# Sheet1.net
KiCad netlist of a schematic drawn in Altium Designer
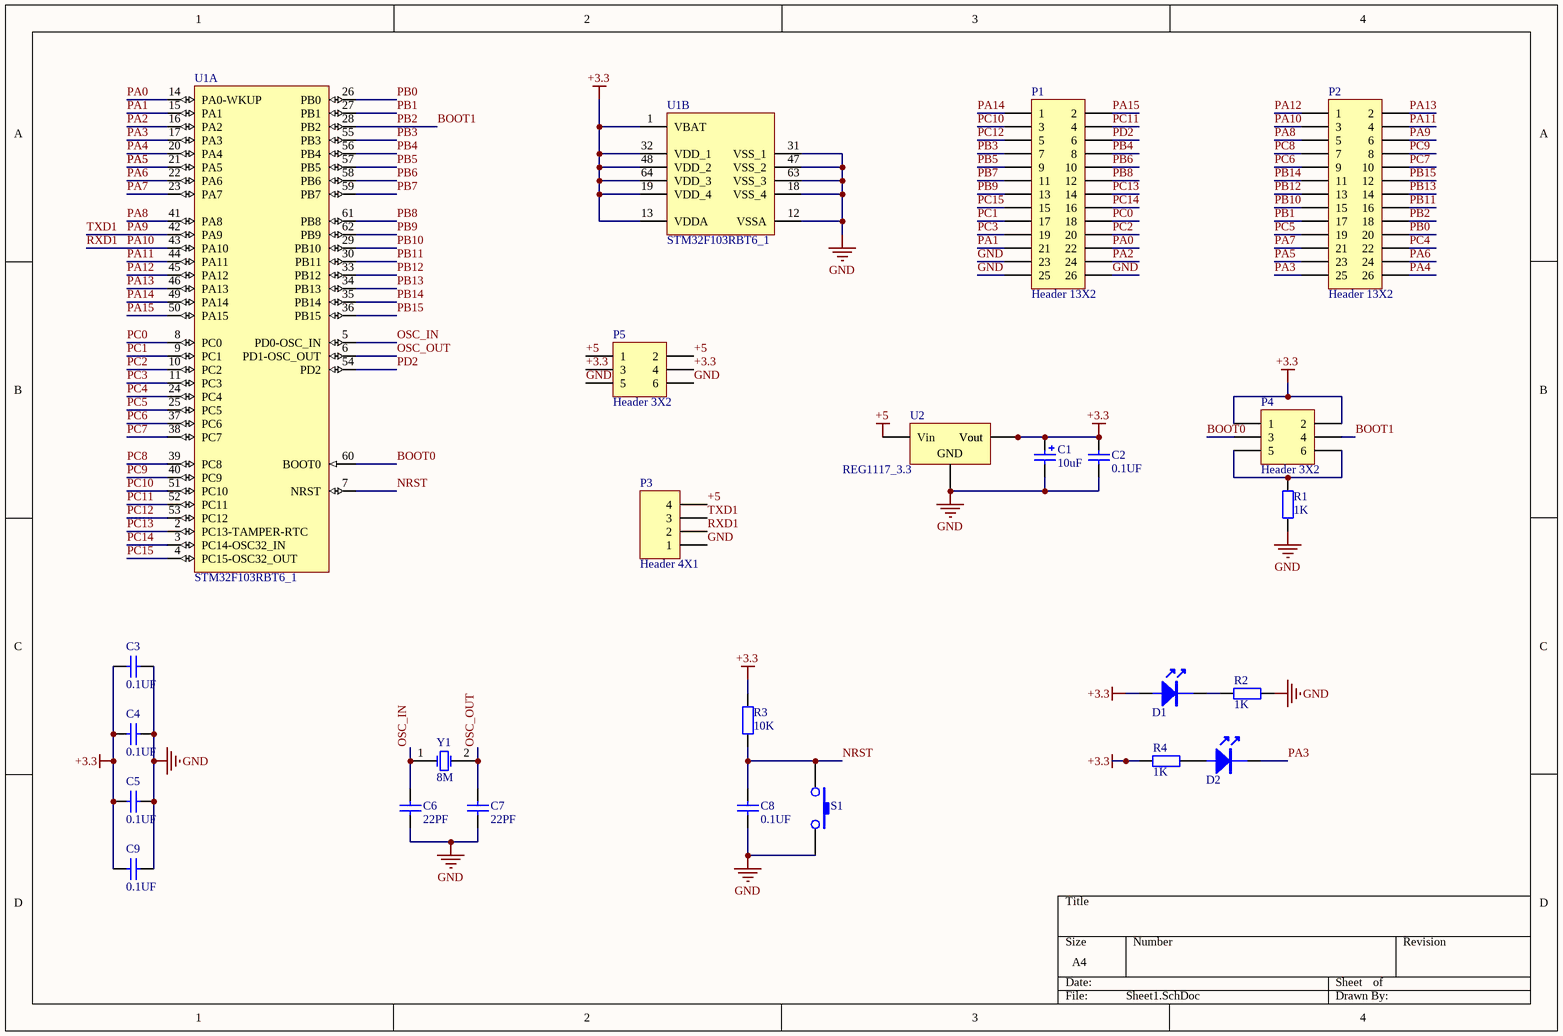
[diagram p0: Sheet1.SchDoc]

(export (version "E")
  (design (tool "Eeschema 10.0.6"))
  (components
    (comp (ref "C1")
      (value "10uF")
      (footprint "0805C")
      (description "Polarized Capacitor (Radial)")
      (fields (field (name "PUBLISHER") "Altium Limited"))
      (libsource (lib "MyLibrary_Lym") (part "Cap Pol"))
    )
    (comp (ref "C2")
      (value "0.1UF")
      (footprint "0805C")
      (description "Capacitor")
      (fields (field (name "PUBLISHER") "Altium Limited"))
      (libsource (lib "MyLibrary_Lym") (part "Cap"))
    )
    (comp (ref "C3")
      (value "0.1UF")
      (footprint "0805C")
      (description "Capacitor")
      (fields (field (name "PUBLISHER") "Altium Limited"))
      (libsource (lib "MyLibrary_Lym") (part "Cap"))
    )
    (comp (ref "C4")
      (value "0.1UF")
      (footprint "0805C")
      (description "Capacitor")
      (fields (field (name "PUBLISHER") "Altium Limited"))
      (libsource (lib "MyLibrary_Lym") (part "Cap"))
    )
    (comp (ref "C5")
      (value "0.1UF")
      (footprint "0805C")
      (description "Capacitor")
      (fields (field (name "PUBLISHER") "Altium Limited"))
      (libsource (lib "MyLibrary_Lym") (part "Cap"))
    )
    (comp (ref "C6")
      (value "22PF")
      (footprint "0805C")
      (description "Capacitor")
      (fields (field (name "PUBLISHER") "Altium Limited"))
      (libsource (lib "MyLibrary_Lym") (part "Cap"))
    )
    (comp (ref "C7")
      (value "22PF")
      (footprint "0805C")
      (description "Capacitor")
      (fields (field (name "PUBLISHER") "Altium Limited"))
      (libsource (lib "MyLibrary_Lym") (part "Cap"))
    )
    (comp (ref "C8")
      (value "0.1UF")
      (footprint "0805C")
      (description "Capacitor")
      (fields (field (name "PUBLISHER") "Altium Limited"))
      (libsource (lib "MyLibrary_Lym") (part "Cap"))
    )
    (comp (ref "C9")
      (value "0.1UF")
      (footprint "0805C")
      (description "Capacitor")
      (fields (field (name "PUBLISHER") "Altium Limited"))
      (libsource (lib "MyLibrary_Lym") (part "Cap"))
    )
    (comp (ref "D1") (value "LED") (footprint "LED0805") (libsource (lib "MyLibrary_Lym") (part "LED")))
    (comp (ref "D2") (value "LED") (footprint "LED0805") (libsource (lib "MyLibrary_Lym") (part "LED")))
    (comp (ref "P1")
      (value "Header 13X2")
      (footprint "HDR2X13")
      (description "Header, 13-Pin, Dual row")
      (fields (field (name "PUBLISHER") "Altium Limited"))
      (libsource (lib "MyLibrary_Lym") (part "Header 13X2"))
    )
    (comp (ref "P2")
      (value "Header 13X2")
      (footprint "HDR2X13")
      (description "Header, 13-Pin, Dual row")
      (fields (field (name "PUBLISHER") "Altium Limited"))
      (libsource (lib "MyLibrary_Lym") (part "Header 13X2"))
    )
    (comp (ref "P3")
      (value "Header 4X1")
      (footprint "HDR1X4")
      (description "Header, 4-Pin, Right Angle")
      (fields (field (name "PUBLISHER") "Altium Limited"))
      (libsource (lib "MyLibrary_Lym") (part "Header 4X1"))
    )
    (comp (ref "P4")
      (value "Header 3X2")
      (footprint "HDR2X3")
      (description "Header, 3-Pin, Dual row")
      (fields (field (name "PUBLISHER") "Altium Limited"))
      (libsource (lib "MyLibrary_Lym") (part "Header 3X2"))
    )
    (comp (ref "P5")
      (value "Header 3X2")
      (footprint "HDR2X3")
      (description "Header, 3-Pin, Dual row")
      (fields (field (name "PUBLISHER") "Altium Limited"))
      (libsource (lib "MyLibrary_Lym") (part "Header 3X2"))
    )
    (comp (ref "R1")
      (value "1K")
      (footprint "0805R")
      (description "Resistor")
      (fields (field (name "PUBLISHER") "Altium Limited"))
      (libsource (lib "") (part "Res_1"))
    )
    (comp (ref "R2")
      (value "1K")
      (footprint "0805R")
      (description "Resistor")
      (fields (field (name "PUBLISHER") "Altium Limited"))
      (libsource (lib "MyLibrary_Lym") (part "Res"))
    )
    (comp (ref "R3")
      (value "10K")
      (footprint "0805R")
      (description "Resistor")
      (fields (field (name "PUBLISHER") "Altium Limited"))
      (libsource (lib "") (part "Res_1"))
    )
    (comp (ref "R4")
      (value "1K")
      (footprint "0805R")
      (description "Resistor")
      (fields (field (name "PUBLISHER") "Altium Limited"))
      (libsource (lib "MyLibrary_Lym") (part "Res"))
    )
    (comp (ref "S1")
      (value "KEY")
      (footprint "KEY_SOP_3X6X2.2MM")
      (libsource (lib "MyLibrary_Lym") (part "KEY"))
    )
    (comp (ref "U1")
      (value "STM32F103RBT6_1")
      (footprint "STM-LQFP64_N")
      (fields (field (name "PARTNUMBER") "STM32F103RBT6"))
      (libsource (lib "MyLibrary_Lym") (part "STM32F103RBT6_1"))
    )
    (comp (ref "U2")
      (value "REG1117_3.3")
      (footprint "SOT223_N")
      (libsource (lib "MyLibrary_Lym") (part "Vlot_Reg"))
    )
    (comp (ref "Y1")
      (value "8M")
      (footprint "OSC2PR-1")
      (description "Crystal Oscillator")
      (fields (field (name "PUBLISHER") "Altium Limited"))
      (libsource (lib "MyLibrary_Lym") (part "XTAL"))
    )
  )
  (nets
    (net (code "1") (name "+3.3") (class "Default")
      (node (ref "C1") (pin "1") (pinfunction "1_1") (pintype "passive"))
      (node (ref "C2") (pin "2") (pinfunction "2_2") (pintype "passive"))
      (node (ref "C3") (pin "2") (pinfunction "2_2") (pintype "passive"))
      (node (ref "C4") (pin "2") (pinfunction "2_2") (pintype "passive"))
      (node (ref "C5") (pin "2") (pinfunction "2_2") (pintype "passive"))
      (node (ref "C9") (pin "2") (pinfunction "2_2") (pintype "passive"))
      (node (ref "D1") (pin "1") (pinfunction "1_1") (pintype "passive"))
      (node (ref "P4") (pin "1") (pinfunction "1_1") (pintype "passive"))
      (node (ref "P4") (pin "2") (pinfunction "2_2") (pintype "passive"))
      (node (ref "P5") (pin "3") (pinfunction "3_3") (pintype "passive"))
      (node (ref "P5") (pin "4") (pinfunction "4_4") (pintype "passive"))
      (node (ref "R3") (pin "2") (pinfunction "2_2") (pintype "passive"))
      (node (ref "R4") (pin "1") (pinfunction "1_1") (pintype "passive"))
      (node (ref "U1") (pin "1") (pinfunction "VBAT_1") (pintype "power_in"))
      (node (ref "U1") (pin "13") (pinfunction "VDDA_13") (pintype "power_in"))
      (node (ref "U1") (pin "19") (pinfunction "VDD_4_19") (pintype "power_in"))
      (node (ref "U1") (pin "32") (pinfunction "VDD_1_32") (pintype "power_in"))
      (node (ref "U1") (pin "48") (pinfunction "VDD_2_48") (pintype "power_in"))
      (node (ref "U1") (pin "64") (pinfunction "VDD_3_64") (pintype "power_in"))
      (node (ref "U2") (pin "3") (pinfunction "Vout_3") (pintype "passive"))
      (node (ref "U2") (pin "4") (pinfunction "Vout_4") (pintype "passive"))
    )
    (net (code "2") (name "+5") (class "Default")
      (node (ref "P3") (pin "4") (pinfunction "4_4") (pintype "passive"))
      (node (ref "P5") (pin "1") (pinfunction "1_1") (pintype "passive"))
      (node (ref "P5") (pin "2") (pinfunction "2_2") (pintype "passive"))
      (node (ref "U2") (pin "1") (pinfunction "Vin_1") (pintype "passive"))
    )
    (net (code "3") (name "/BOOT0") (class "Default")
      (node (ref "P4") (pin "3") (pinfunction "3_3") (pintype "passive"))
      (node (ref "U1") (pin "60") (pinfunction "BOOT0_60") (pintype "input"))
    )
    (net (code "4") (name "/BOOT1") (class "Default")
      (node (ref "P2") (pin "18") (pinfunction "18_18") (pintype "passive"))
      (node (ref "P4") (pin "4") (pinfunction "4_4") (pintype "passive"))
      (node (ref "U1") (pin "28") (pinfunction "PB2_28") (pintype "bidirectional"))
    )
    (net (code "5") (name "/NRST") (class "Default")
      (node (ref "C8") (pin "1") (pinfunction "1_1") (pintype "passive"))
      (node (ref "R3") (pin "1") (pinfunction "1_1") (pintype "passive"))
      (node (ref "S1") (pin "1") (pinfunction "1_1") (pintype "passive"))
      (node (ref "U1") (pin "7") (pinfunction "NRST_7") (pintype "bidirectional"))
    )
    (net (code "6") (name "/OSC_IN") (class "Default")
      (node (ref "C6") (pin "1") (pinfunction "1_1") (pintype "passive"))
      (node (ref "U1") (pin "5") (pinfunction "PD0-OSC_IN_5") (pintype "bidirectional"))
      (node (ref "Y1") (pin "1") (pinfunction "OSC1_1") (pintype "passive"))
    )
    (net (code "7") (name "/OSC_OUT") (class "Default")
      (node (ref "C7") (pin "1") (pinfunction "1_1") (pintype "passive"))
      (node (ref "U1") (pin "6") (pinfunction "PD1-OSC_OUT_6") (pintype "bidirectional"))
      (node (ref "Y1") (pin "2") (pinfunction "OSC2_2") (pintype "passive"))
    )
    (net (code "8") (name "/PA0") (class "Default")
      (node (ref "P1") (pin "22") (pinfunction "22_22") (pintype "passive"))
      (node (ref "U1") (pin "14") (pinfunction "PA0-WKUP_14") (pintype "bidirectional"))
    )
    (net (code "9") (name "/PA1") (class "Default")
      (node (ref "P1") (pin "21") (pinfunction "21_21") (pintype "passive"))
      (node (ref "U1") (pin "15") (pinfunction "PA1_15") (pintype "bidirectional"))
    )
    (net (code "10") (name "/PA2") (class "Default")
      (node (ref "P1") (pin "24") (pinfunction "24_24") (pintype "passive"))
      (node (ref "U1") (pin "16") (pinfunction "PA2_16") (pintype "bidirectional"))
    )
    (net (code "11") (name "/PA3") (class "Default")
      (node (ref "D2") (pin "2") (pinfunction "2_2") (pintype "passive"))
      (node (ref "P2") (pin "25") (pinfunction "25_25") (pintype "passive"))
      (node (ref "U1") (pin "17") (pinfunction "PA3_17") (pintype "bidirectional"))
    )
    (net (code "12") (name "/PA4") (class "Default")
      (node (ref "P2") (pin "26") (pinfunction "26_26") (pintype "passive"))
      (node (ref "U1") (pin "20") (pinfunction "PA4_20") (pintype "bidirectional"))
    )
    (net (code "13") (name "/PA5") (class "Default")
      (node (ref "P2") (pin "23") (pinfunction "23_23") (pintype "passive"))
      (node (ref "U1") (pin "21") (pinfunction "PA5_21") (pintype "bidirectional"))
    )
    (net (code "14") (name "/PA6") (class "Default")
      (node (ref "P2") (pin "24") (pinfunction "24_24") (pintype "passive"))
      (node (ref "U1") (pin "22") (pinfunction "PA6_22") (pintype "bidirectional"))
    )
    (net (code "15") (name "/PA7") (class "Default")
      (node (ref "P2") (pin "21") (pinfunction "21_21") (pintype "passive"))
      (node (ref "U1") (pin "23") (pinfunction "PA7_23") (pintype "bidirectional"))
    )
    (net (code "16") (name "/PA8") (class "Default")
      (node (ref "P2") (pin "5") (pinfunction "5_5") (pintype "passive"))
      (node (ref "U1") (pin "41") (pinfunction "PA8_41") (pintype "bidirectional"))
    )
    (net (code "17") (name "/PA9") (class "Default")
      (node (ref "P2") (pin "6") (pinfunction "6_6") (pintype "passive"))
      (node (ref "P3") (pin "3") (pinfunction "3_3") (pintype "passive"))
      (node (ref "U1") (pin "42") (pinfunction "PA9_42") (pintype "bidirectional"))
    )
    (net (code "18") (name "/PA10") (class "Default")
      (node (ref "P2") (pin "3") (pinfunction "3_3") (pintype "passive"))
      (node (ref "P3") (pin "2") (pinfunction "2_2") (pintype "passive"))
      (node (ref "U1") (pin "43") (pinfunction "PA10_43") (pintype "bidirectional"))
    )
    (net (code "19") (name "/PA11") (class "Default")
      (node (ref "P2") (pin "4") (pinfunction "4_4") (pintype "passive"))
      (node (ref "U1") (pin "44") (pinfunction "PA11_44") (pintype "bidirectional"))
    )
    (net (code "20") (name "/PA12") (class "Default")
      (node (ref "P2") (pin "1") (pinfunction "1_1") (pintype "passive"))
      (node (ref "U1") (pin "45") (pinfunction "PA12_45") (pintype "bidirectional"))
    )
    (net (code "21") (name "/PA13") (class "Default")
      (node (ref "P2") (pin "2") (pinfunction "2_2") (pintype "passive"))
      (node (ref "U1") (pin "46") (pinfunction "PA13_46") (pintype "bidirectional"))
    )
    (net (code "22") (name "/PA14") (class "Default")
      (node (ref "P1") (pin "1") (pinfunction "1_1") (pintype "passive"))
      (node (ref "U1") (pin "49") (pinfunction "PA14_49") (pintype "bidirectional"))
    )
    (net (code "23") (name "/PA15") (class "Default")
      (node (ref "P1") (pin "2") (pinfunction "2_2") (pintype "passive"))
      (node (ref "U1") (pin "50") (pinfunction "PA15_50") (pintype "bidirectional"))
    )
    (net (code "24") (name "/PB0") (class "Default")
      (node (ref "P2") (pin "20") (pinfunction "20_20") (pintype "passive"))
      (node (ref "U1") (pin "26") (pinfunction "PB0_26") (pintype "bidirectional"))
    )
    (net (code "25") (name "/PB1") (class "Default")
      (node (ref "P2") (pin "17") (pinfunction "17_17") (pintype "passive"))
      (node (ref "U1") (pin "27") (pinfunction "PB1_27") (pintype "bidirectional"))
    )
    (net (code "26") (name "/PB3") (class "Default")
      (node (ref "P1") (pin "7") (pinfunction "7_7") (pintype "passive"))
      (node (ref "U1") (pin "55") (pinfunction "PB3_55") (pintype "bidirectional"))
    )
    (net (code "27") (name "/PB4") (class "Default")
      (node (ref "P1") (pin "8") (pinfunction "8_8") (pintype "passive"))
      (node (ref "U1") (pin "56") (pinfunction "PB4_56") (pintype "bidirectional"))
    )
    (net (code "28") (name "/PB5") (class "Default")
      (node (ref "P1") (pin "9") (pinfunction "9_9") (pintype "passive"))
      (node (ref "U1") (pin "57") (pinfunction "PB5_57") (pintype "bidirectional"))
    )
    (net (code "29") (name "/PB6") (class "Default")
      (node (ref "P1") (pin "10") (pinfunction "10_10") (pintype "passive"))
      (node (ref "U1") (pin "58") (pinfunction "PB6_58") (pintype "bidirectional"))
    )
    (net (code "30") (name "/PB7") (class "Default")
      (node (ref "P1") (pin "11") (pinfunction "11_11") (pintype "passive"))
      (node (ref "U1") (pin "59") (pinfunction "PB7_59") (pintype "bidirectional"))
    )
    (net (code "31") (name "/PB8") (class "Default")
      (node (ref "P1") (pin "12") (pinfunction "12_12") (pintype "passive"))
      (node (ref "U1") (pin "61") (pinfunction "PB8_61") (pintype "bidirectional"))
    )
    (net (code "32") (name "/PB9") (class "Default")
      (node (ref "P1") (pin "13") (pinfunction "13_13") (pintype "passive"))
      (node (ref "U1") (pin "62") (pinfunction "PB9_62") (pintype "bidirectional"))
    )
    (net (code "33") (name "/PB10") (class "Default")
      (node (ref "P2") (pin "15") (pinfunction "15_15") (pintype "passive"))
      (node (ref "U1") (pin "29") (pinfunction "PB10_29") (pintype "bidirectional"))
    )
    (net (code "34") (name "/PB11") (class "Default")
      (node (ref "P2") (pin "16") (pinfunction "16_16") (pintype "passive"))
      (node (ref "U1") (pin "30") (pinfunction "PB11_30") (pintype "bidirectional"))
    )
    (net (code "35") (name "/PB12") (class "Default")
      (node (ref "P2") (pin "13") (pinfunction "13_13") (pintype "passive"))
      (node (ref "U1") (pin "33") (pinfunction "PB12_33") (pintype "bidirectional"))
    )
    (net (code "36") (name "/PB13") (class "Default")
      (node (ref "P2") (pin "14") (pinfunction "14_14") (pintype "passive"))
      (node (ref "U1") (pin "34") (pinfunction "PB13_34") (pintype "bidirectional"))
    )
    (net (code "37") (name "/PB14") (class "Default")
      (node (ref "P2") (pin "11") (pinfunction "11_11") (pintype "passive"))
      (node (ref "U1") (pin "35") (pinfunction "PB14_35") (pintype "bidirectional"))
    )
    (net (code "38") (name "/PB15") (class "Default")
      (node (ref "P2") (pin "12") (pinfunction "12_12") (pintype "passive"))
      (node (ref "U1") (pin "36") (pinfunction "PB15_36") (pintype "bidirectional"))
    )
    (net (code "39") (name "/PC0") (class "Default")
      (node (ref "P1") (pin "18") (pinfunction "18_18") (pintype "passive"))
      (node (ref "U1") (pin "8") (pinfunction "PC0_8") (pintype "bidirectional"))
    )
    (net (code "40") (name "/PC1") (class "Default")
      (node (ref "P1") (pin "17") (pinfunction "17_17") (pintype "passive"))
      (node (ref "U1") (pin "9") (pinfunction "PC1_9") (pintype "bidirectional"))
    )
    (net (code "41") (name "/PC2") (class "Default")
      (node (ref "P1") (pin "20") (pinfunction "20_20") (pintype "passive"))
      (node (ref "U1") (pin "10") (pinfunction "PC2_10") (pintype "bidirectional"))
    )
    (net (code "42") (name "/PC3") (class "Default")
      (node (ref "P1") (pin "19") (pinfunction "19_19") (pintype "passive"))
      (node (ref "U1") (pin "11") (pinfunction "PC3_11") (pintype "bidirectional"))
    )
    (net (code "43") (name "/PC4") (class "Default")
      (node (ref "P2") (pin "22") (pinfunction "22_22") (pintype "passive"))
      (node (ref "U1") (pin "24") (pinfunction "PC4_24") (pintype "bidirectional"))
    )
    (net (code "44") (name "/PC5") (class "Default")
      (node (ref "P2") (pin "19") (pinfunction "19_19") (pintype "passive"))
      (node (ref "U1") (pin "25") (pinfunction "PC5_25") (pintype "bidirectional"))
    )
    (net (code "45") (name "/PC6") (class "Default")
      (node (ref "P2") (pin "9") (pinfunction "9_9") (pintype "passive"))
      (node (ref "U1") (pin "37") (pinfunction "PC6_37") (pintype "bidirectional"))
    )
    (net (code "46") (name "/PC7") (class "Default")
      (node (ref "P2") (pin "10") (pinfunction "10_10") (pintype "passive"))
      (node (ref "U1") (pin "38") (pinfunction "PC7_38") (pintype "bidirectional"))
    )
    (net (code "47") (name "/PC8") (class "Default")
      (node (ref "P2") (pin "7") (pinfunction "7_7") (pintype "passive"))
      (node (ref "U1") (pin "39") (pinfunction "PC8_39") (pintype "bidirectional"))
    )
    (net (code "48") (name "/PC9") (class "Default")
      (node (ref "P2") (pin "8") (pinfunction "8_8") (pintype "passive"))
      (node (ref "U1") (pin "40") (pinfunction "PC9_40") (pintype "bidirectional"))
    )
    (net (code "49") (name "/PC10") (class "Default")
      (node (ref "P1") (pin "3") (pinfunction "3_3") (pintype "passive"))
      (node (ref "U1") (pin "51") (pinfunction "PC10_51") (pintype "bidirectional"))
    )
    (net (code "50") (name "/PC11") (class "Default")
      (node (ref "P1") (pin "4") (pinfunction "4_4") (pintype "passive"))
      (node (ref "U1") (pin "52") (pinfunction "PC11_52") (pintype "bidirectional"))
    )
    (net (code "51") (name "/PC12") (class "Default")
      (node (ref "P1") (pin "5") (pinfunction "5_5") (pintype "passive"))
      (node (ref "U1") (pin "53") (pinfunction "PC12_53") (pintype "bidirectional"))
    )
    (net (code "52") (name "/PC13") (class "Default")
      (node (ref "P1") (pin "14") (pinfunction "14_14") (pintype "passive"))
      (node (ref "U1") (pin "2") (pinfunction "PC13-TAMPER-RTC_2") (pintype "bidirectional"))
    )
    (net (code "53") (name "/PC14") (class "Default")
      (node (ref "P1") (pin "16") (pinfunction "16_16") (pintype "passive"))
      (node (ref "U1") (pin "3") (pinfunction "PC14-OSC32_IN_3") (pintype "bidirectional"))
    )
    (net (code "54") (name "/PC15") (class "Default")
      (node (ref "P1") (pin "15") (pinfunction "15_15") (pintype "passive"))
      (node (ref "U1") (pin "4") (pinfunction "PC15-OSC32_OUT_4") (pintype "bidirectional"))
    )
    (net (code "55") (name "/PD2") (class "Default")
      (node (ref "P1") (pin "6") (pinfunction "6_6") (pintype "passive"))
      (node (ref "U1") (pin "54") (pinfunction "PD2_54") (pintype "bidirectional"))
    )
    (net (code "56") (name "GND") (class "Default")
      (node (ref "C1") (pin "2") (pinfunction "2_2") (pintype "passive"))
      (node (ref "C2") (pin "1") (pinfunction "1_1") (pintype "passive"))
      (node (ref "C3") (pin "1") (pinfunction "1_1") (pintype "passive"))
      (node (ref "C4") (pin "1") (pinfunction "1_1") (pintype "passive"))
      (node (ref "C5") (pin "1") (pinfunction "1_1") (pintype "passive"))
      (node (ref "C6") (pin "2") (pinfunction "2_2") (pintype "passive"))
      (node (ref "C7") (pin "2") (pinfunction "2_2") (pintype "passive"))
      (node (ref "C8") (pin "2") (pinfunction "2_2") (pintype "passive"))
      (node (ref "C9") (pin "1") (pinfunction "1_1") (pintype "passive"))
      (node (ref "P1") (pin "23") (pinfunction "23_23") (pintype "passive"))
      (node (ref "P1") (pin "25") (pinfunction "25_25") (pintype "passive"))
      (node (ref "P1") (pin "26") (pinfunction "26_26") (pintype "passive"))
      (node (ref "P3") (pin "1") (pinfunction "1_1") (pintype "passive"))
      (node (ref "P5") (pin "5") (pinfunction "5_5") (pintype "passive"))
      (node (ref "P5") (pin "6") (pinfunction "6_6") (pintype "passive"))
      (node (ref "R1") (pin "1") (pinfunction "1_1") (pintype "passive"))
      (node (ref "R2") (pin "2") (pinfunction "2_2") (pintype "passive"))
      (node (ref "S1") (pin "2") (pinfunction "2_2") (pintype "passive"))
      (node (ref "U1") (pin "12") (pinfunction "VSSA_12") (pintype "power_in"))
      (node (ref "U1") (pin "18") (pinfunction "VSS_4_18") (pintype "power_in"))
      (node (ref "U1") (pin "31") (pinfunction "VSS_1_31") (pintype "power_in"))
      (node (ref "U1") (pin "47") (pinfunction "VSS_2_47") (pintype "power_in"))
      (node (ref "U1") (pin "63") (pinfunction "VSS_3_63") (pintype "power_in"))
      (node (ref "U2") (pin "2") (pinfunction "GND_2") (pintype "passive"))
    )
    (net (code "57") (name "Net-(D1-Pad2)") (class "Default")
      (node (ref "D1") (pin "2") (pinfunction "2_2") (pintype "passive"))
      (node (ref "R2") (pin "1") (pinfunction "1_1") (pintype "passive"))
    )
    (net (code "58") (name "Net-(D2-Pad1)") (class "Default")
      (node (ref "D2") (pin "1") (pinfunction "1_1") (pintype "passive"))
      (node (ref "R4") (pin "2") (pinfunction "2_2") (pintype "passive"))
    )
    (net (code "59") (name "Net-(P4-Pad5)") (class "Default")
      (node (ref "P4") (pin "5") (pinfunction "5_5") (pintype "passive"))
      (node (ref "P4") (pin "6") (pinfunction "6_6") (pintype "passive"))
      (node (ref "R1") (pin "2") (pinfunction "2_2") (pintype "passive"))
    )
  )
)
